# MM24I.net
KiCad netlist of a schematic drawn in EAGLE
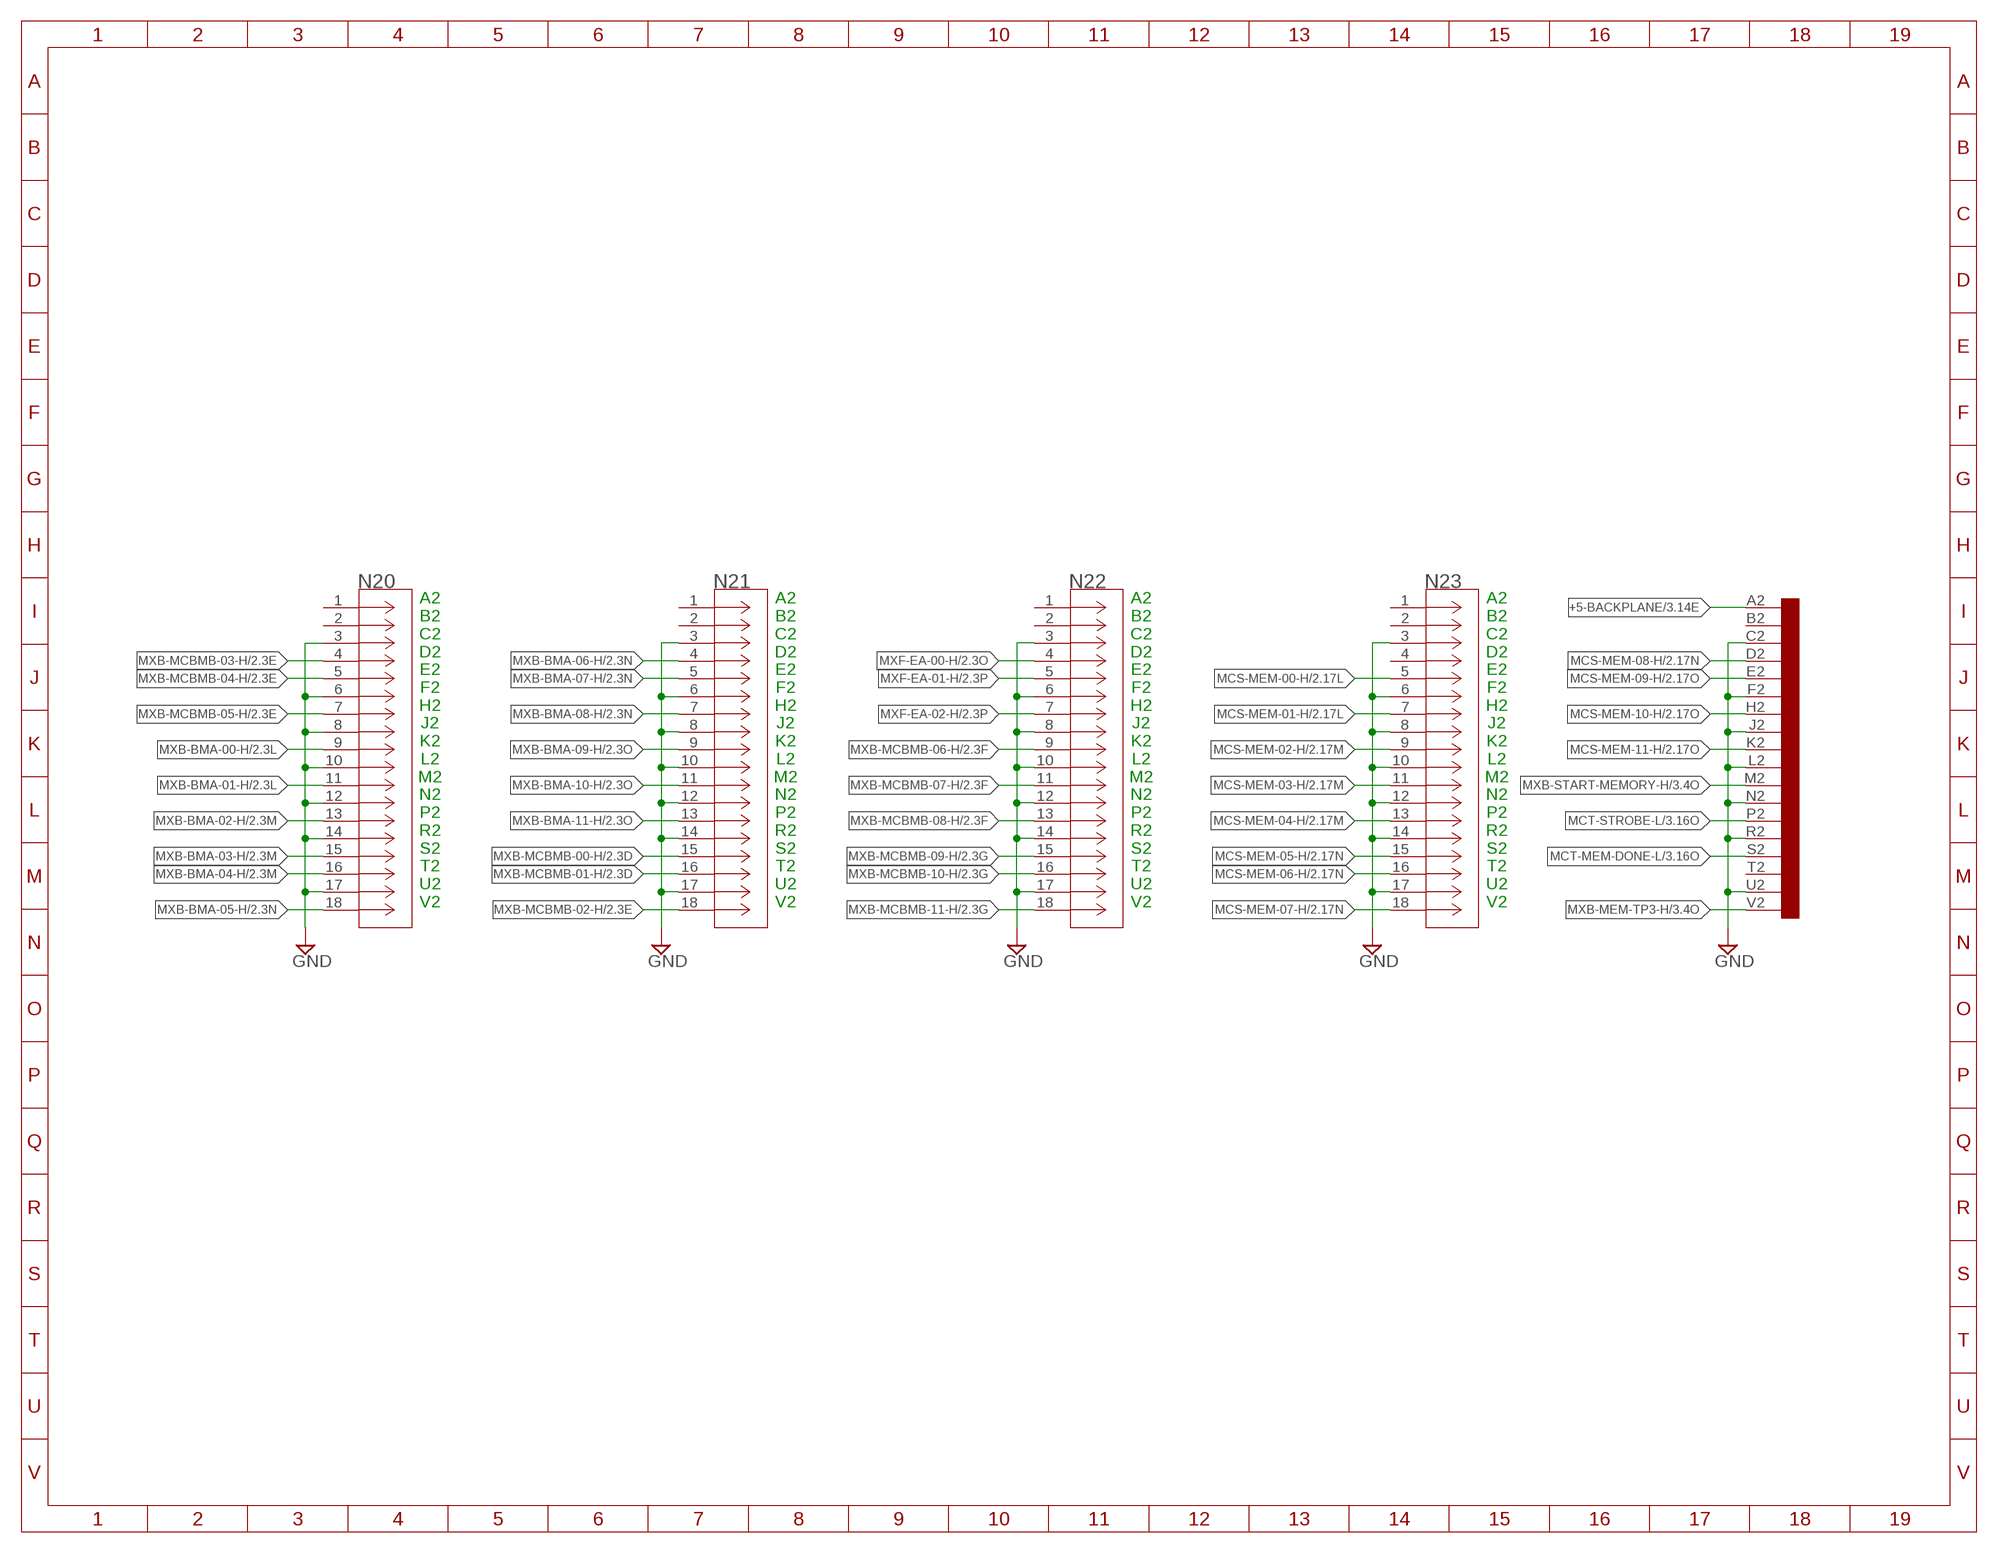
[diagram p0: schematic, sheet 1]
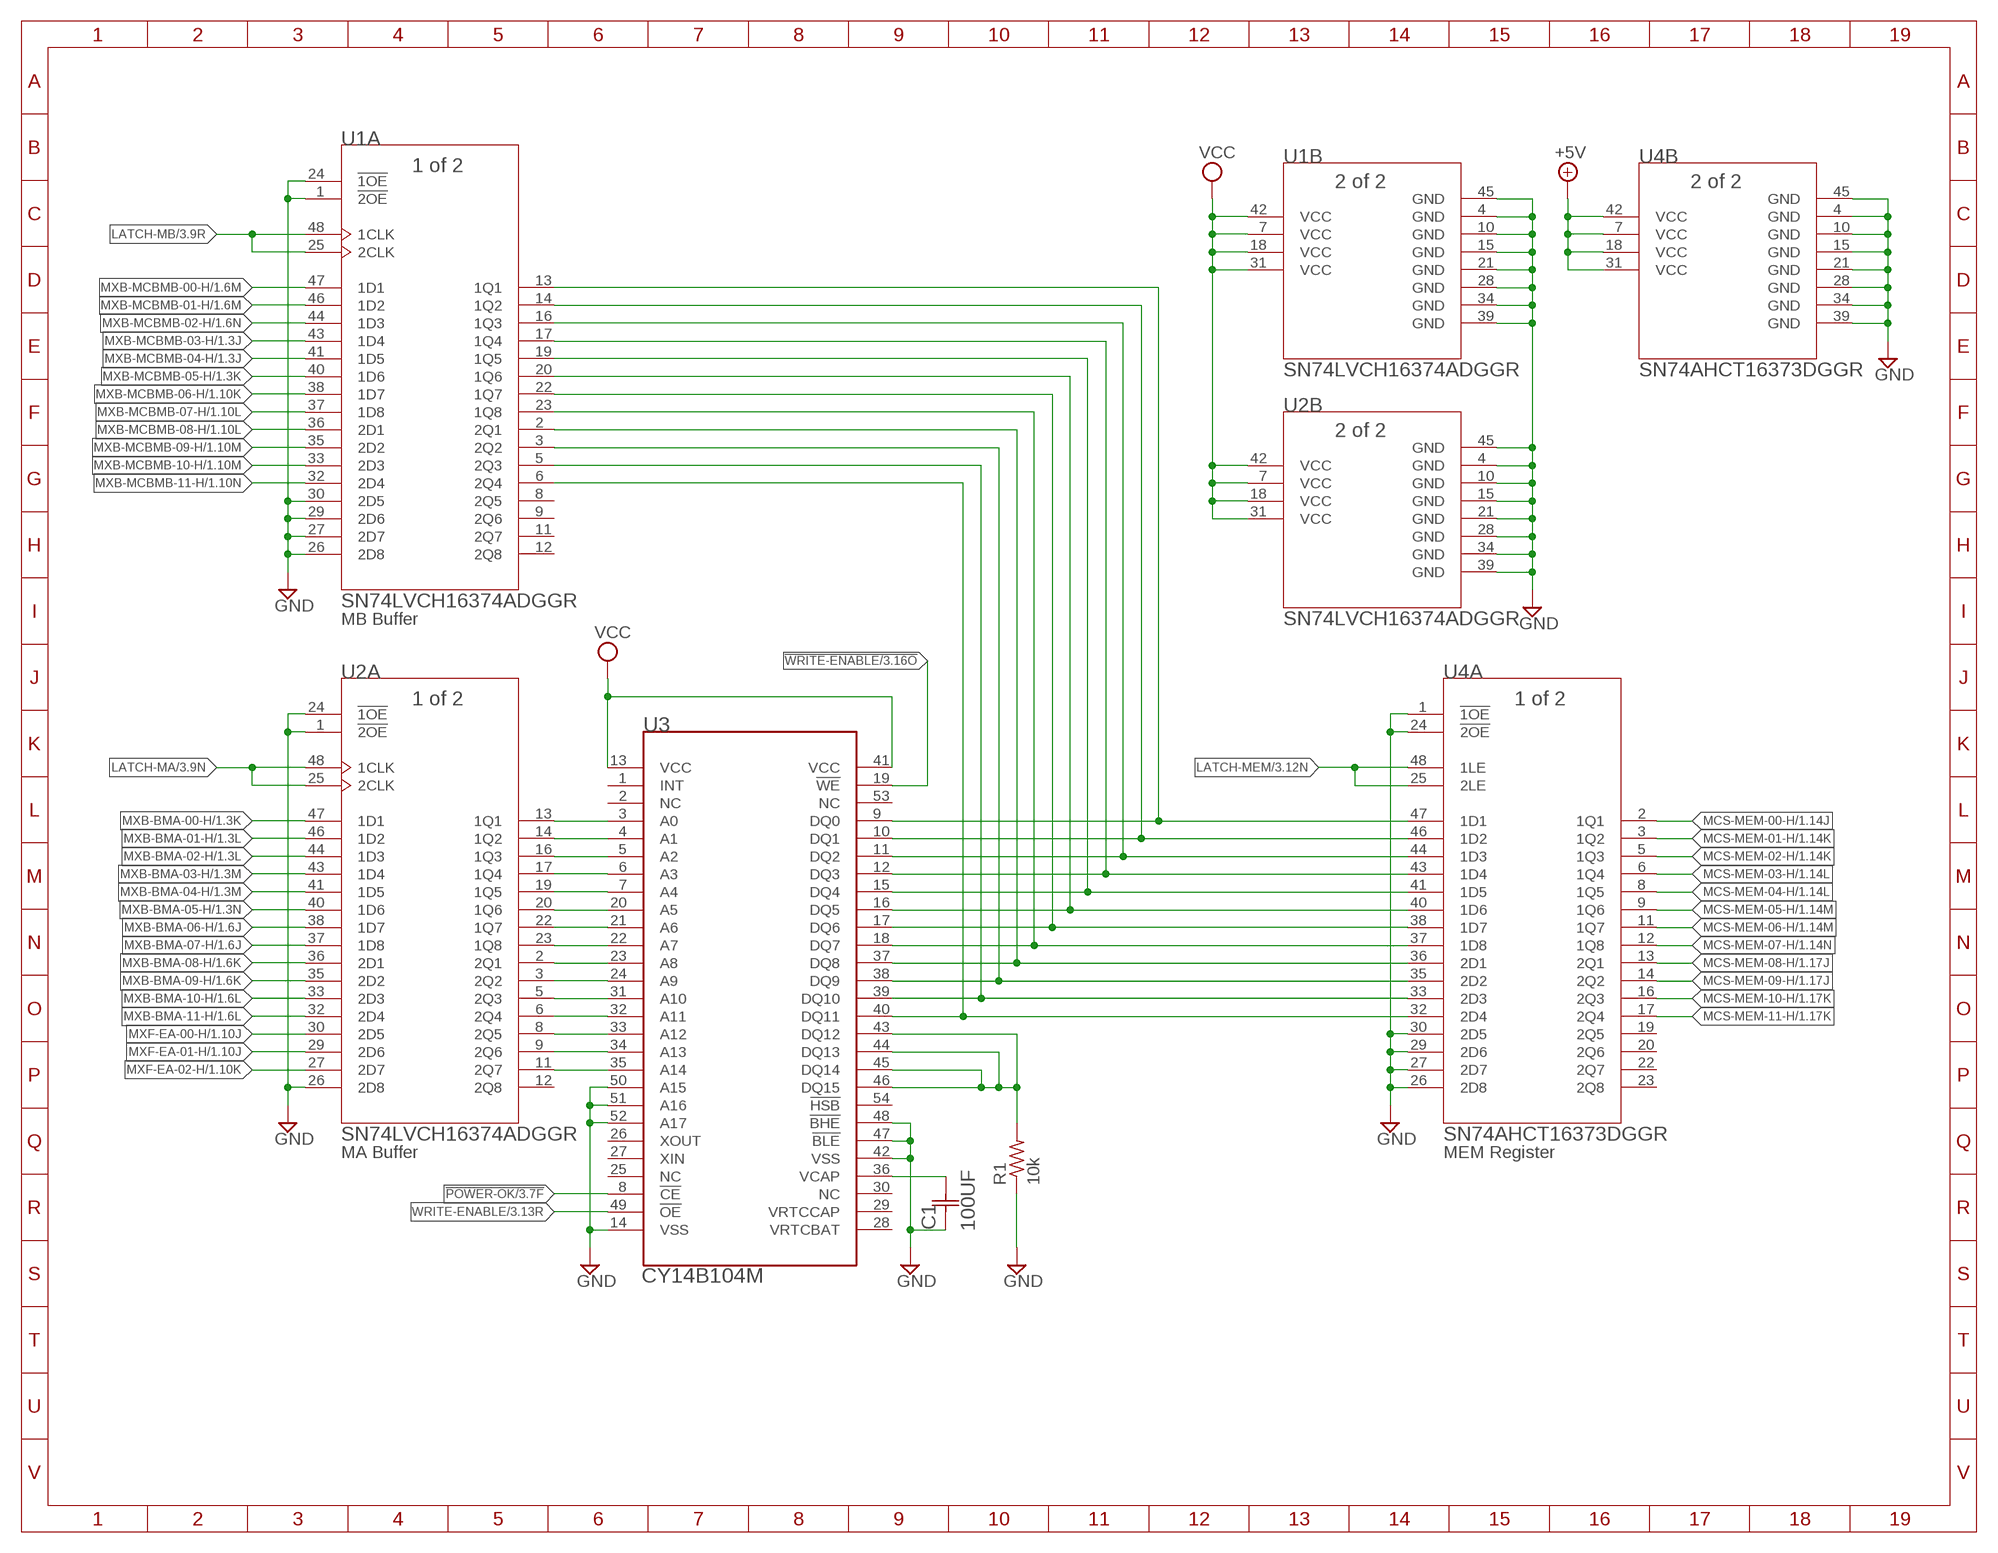
[diagram p1: schematic, sheet 2]
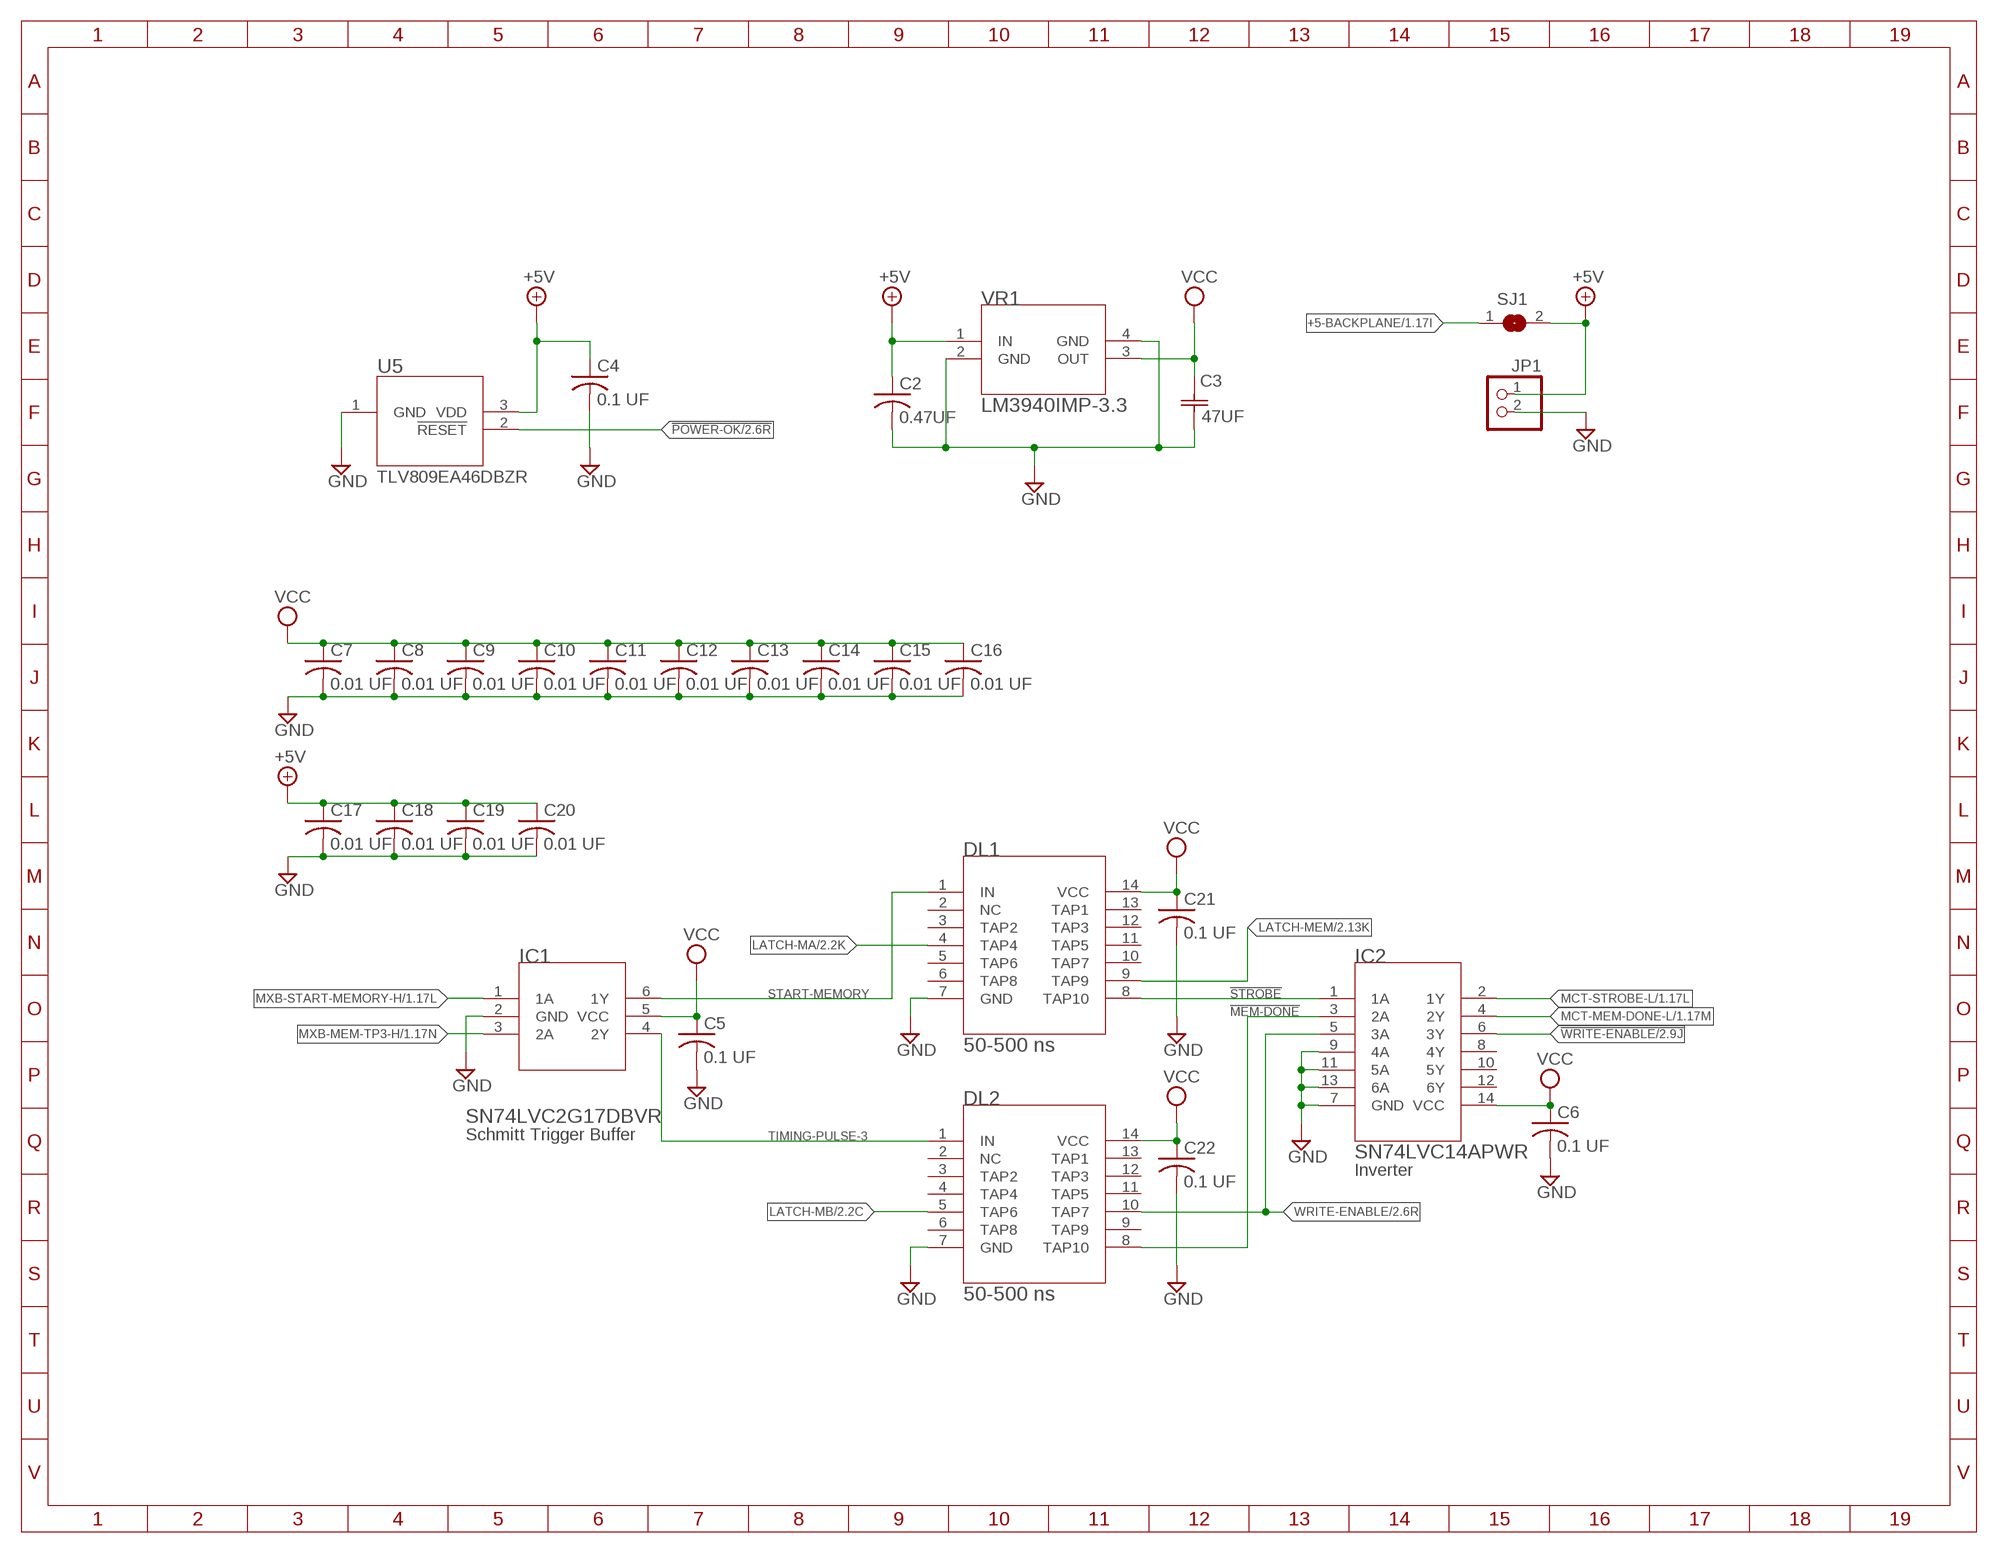
[diagram p2: schematic, sheet 3]

(export (version "E")
  (design (tool "Eeschema 10.0.6"))
  (components
    (comp (ref "C2")
      (value "0.47UF")
      (footprint "eagle-import:C0805")
      (libsource (lib "eagle-import") (part "C-USC0805"))
    )
    (comp (ref "C3")
      (value "47UF")
      (footprint "eagle-import:NOJC")
      (fields (field (name "MANUFACTURER_PART_NUMBER") "NOJC476M010RWJ"))
      (libsource (lib "eagle-import") (part "NOJC476M010RWJ"))
    )
    (comp (ref "C4")
      (value "0.1 UF")
      (footprint "eagle-import:C0402")
      (libsource (lib "eagle-import") (part "C-USC0402"))
    )
    (comp (ref "C5")
      (value "0.1 UF")
      (footprint "eagle-import:C0402")
      (libsource (lib "eagle-import") (part "C-USC0402"))
    )
    (comp (ref "C6")
      (value "0.1 UF")
      (footprint "eagle-import:C0402")
      (libsource (lib "eagle-import") (part "C-USC0402"))
    )
    (comp (ref "C7")
      (value "0.01 UF")
      (footprint "eagle-import:C0402")
      (libsource (lib "eagle-import") (part "C-USC0402"))
    )
    (comp (ref "C8")
      (value "0.01 UF")
      (footprint "eagle-import:C0402")
      (libsource (lib "eagle-import") (part "C-USC0402"))
    )
    (comp (ref "C9")
      (value "0.01 UF")
      (footprint "eagle-import:C0402")
      (libsource (lib "eagle-import") (part "C-USC0402"))
    )
    (comp (ref "C10")
      (value "0.01 UF")
      (footprint "eagle-import:C0402")
      (libsource (lib "eagle-import") (part "C-USC0402"))
    )
    (comp (ref "C11")
      (value "0.01 UF")
      (footprint "eagle-import:C0402")
      (libsource (lib "eagle-import") (part "C-USC0402"))
    )
    (comp (ref "C12")
      (value "0.01 UF")
      (footprint "eagle-import:C0402")
      (libsource (lib "eagle-import") (part "C-USC0402"))
    )
    (comp (ref "C13")
      (value "0.01 UF")
      (footprint "eagle-import:C0402")
      (libsource (lib "eagle-import") (part "C-USC0402"))
    )
    (comp (ref "C14")
      (value "0.01 UF")
      (footprint "eagle-import:C0402")
      (libsource (lib "eagle-import") (part "C-USC0402"))
    )
    (comp (ref "C15")
      (value "0.01 UF")
      (footprint "eagle-import:C0402")
      (libsource (lib "eagle-import") (part "C-USC0402"))
    )
    (comp (ref "C16")
      (value "0.01 UF")
      (footprint "eagle-import:C0402")
      (libsource (lib "eagle-import") (part "C-USC0402"))
    )
    (comp (ref "C17")
      (value "0.01 UF")
      (footprint "eagle-import:C0402")
      (libsource (lib "eagle-import") (part "C-USC0402"))
    )
    (comp (ref "C18")
      (value "0.01 UF")
      (footprint "eagle-import:C0402")
      (libsource (lib "eagle-import") (part "C-USC0402"))
    )
    (comp (ref "C19")
      (value "0.01 UF")
      (footprint "eagle-import:C0402")
      (libsource (lib "eagle-import") (part "C-USC0402"))
    )
    (comp (ref "C20")
      (value "0.01 UF")
      (footprint "eagle-import:C0402")
      (libsource (lib "eagle-import") (part "C-USC0402"))
    )
    (comp (ref "C21")
      (value "0.1 UF")
      (footprint "eagle-import:C0402")
      (libsource (lib "eagle-import") (part "C-USC0402"))
    )
    (comp (ref "C22")
      (value "0.1 UF")
      (footprint "eagle-import:C0402")
      (libsource (lib "eagle-import") (part "C-USC0402"))
    )
    (comp (ref "DL1")
      (value "50-500 ns")
      (footprint "eagle-import:21-0066J_14")
      (fields (field (name "MANUFACTURER_PART_NUMBER") "DS1110LE-100+"))
      (libsource (lib "eagle-import") (part "DS1110LE-500+"))
    )
    (comp (ref "DL2")
      (value "50-500 ns")
      (footprint "eagle-import:21-0066J_14")
      (fields (field (name "MANUFACTURER_PART_NUMBER") "DS1110LE-100+"))
      (libsource (lib "eagle-import") (part "DS1110LE-500+"))
    )
    (comp (ref "IC1")
      (value "SN74LVC2G17DBVR")
      (footprint "eagle-import:DBV6")
      (fields (field (name "MANUFACTURER") "Texas Instruments"))
      (libsource (lib "eagle-import") (part "SN74LVC2G17DBVR"))
    )
    (comp (ref "IC2")
      (value "SN74LVC14APWR")
      (footprint "eagle-import:PW14")
      (fields (field (name "MANUFACTURER") "Texas Instruments"))
      (libsource (lib "eagle-import") (part "SN74LVC14APWR"))
    )
    (comp (ref "JP1")
      (value "PINHD-1X2")
      (footprint "eagle-import:1X02")
      (libsource (lib "eagle-import") (part "PINHD-1X2"))
    )
    (comp (ref "SJ1") (value "SJ") (footprint "eagle-import:SJ") (libsource (lib "eagle-import") (part "SJ")))
    (comp (ref "U5")
      (value "TLV809EA46DBZR")
      (footprint "eagle-import:DBZ3")
      (fields (field (name "MANUFACTURER") "Texas Instruments"))
      (libsource (lib "eagle-import") (part "TLV809EA46DBZR"))
    )
    (comp (ref "VR1")
      (value "LM3940IMP-3.3")
      (footprint "eagle-import:MP04A")
      (fields (field (name "MANUFACTURER_PART_NUMBER") "LM3940IMP-3.3/NOPB"))
      (libsource (lib "eagle-import") (part "LM3940IMP-3.3"))
    )
    (comp (ref "N20")
      (value "FH12-18S-0.5SV(55)")
      (footprint "eagle-import:CON18_1X18_DUTB_HRS")
      (libsource (lib "eagle-import") (part "FH12-18S-0.5SV(55)"))
    )
    (comp (ref "N21")
      (value "FH12-18S-0.5SV(55)")
      (footprint "eagle-import:CON18_1X18_DUTB_HRS")
      (libsource (lib "eagle-import") (part "FH12-18S-0.5SV(55)"))
    )
    (comp (ref "N22")
      (value "FH12-18S-0.5SV(55)")
      (footprint "eagle-import:CON18_1X18_DUTB_HRS")
      (libsource (lib "eagle-import") (part "FH12-18S-0.5SV(55)"))
    )
    (comp (ref "N23")
      (value "FH12-18S-0.5SV(55)")
      (footprint "eagle-import:CON18_1X18_DUTB_HRS")
      (libsource (lib "eagle-import") (part "FH12-18S-0.5SV(55)"))
    )
    (comp (ref "U$1")
      (value "SINGLE")
      (footprint "eagle-import:EDGE-CON2")
      (libsource (lib "eagle-import") (part "SINGLE"))
    )
    (comp (ref "C1")
      (value "100UF")
      (footprint "eagle-import:CAPCP7343X430N")
      (fields (field (name "MPN") "NOJD107M010RWJ"))
      (libsource (lib "eagle-import") (part "NOJD107M010RWJ"))
    )
    (comp (ref "R1")
      (value "10k")
      (footprint "eagle-import:R0402")
      (libsource (lib "eagle-import") (part "R-US_R0402"))
    )
    (comp (ref "U1")
      (value "SN74LVCH16374ADGGR")
      (footprint "eagle-import:DGG48")
      (libsource (lib "eagle-import") (part "SN74LVCH16374ADGGR"))
    )
    (comp (ref "U2")
      (value "SN74LVCH16374ADGGR")
      (footprint "eagle-import:DGG48")
      (libsource (lib "eagle-import") (part "SN74LVCH16374ADGGR"))
    )
    (comp (ref "U3")
      (value "CY14B104M")
      (footprint "eagle-import:TSOPII-54")
      (libsource (lib "eagle-import") (part "CY14B104M"))
    )
    (comp (ref "U4")
      (value "SN74AHCT16373DGGR")
      (footprint "eagle-import:DGG48")
      (fields (field (name "MANUFACTURER") "Texas Instruments"))
      (libsource (lib "eagle-import") (part "SN74AHCT16373DGGR"))
    )
  )
  (nets
    (net (code "1") (name "+5-BACKPLANE") (class "Default")
      (node (ref "SJ1") (pin "1") (pinfunction "1_1") (pintype "passive"))
      (node (ref "U$1") (pin "A2") (pinfunction "1_A2") (pintype "bidirectional"))
    )
    (net (code "2") (name "+5V") (class "Default")
      (node (ref "C17") (pin "1") (pinfunction "1_1") (pintype "passive"))
      (node (ref "C18") (pin "1") (pinfunction "1_1") (pintype "passive"))
      (node (ref "C19") (pin "1") (pinfunction "1_1") (pintype "passive"))
      (node (ref "C2") (pin "1") (pinfunction "1_1") (pintype "passive"))
      (node (ref "C20") (pin "1") (pinfunction "1_1") (pintype "passive"))
      (node (ref "C4") (pin "1") (pinfunction "1_1") (pintype "passive"))
      (node (ref "JP1") (pin "1") (pinfunction "1_1") (pintype "passive"))
      (node (ref "SJ1") (pin "2") (pinfunction "2_2") (pintype "passive"))
      (node (ref "U4") (pin "18") (pinfunction "VCC_18") (pintype "power_in"))
      (node (ref "U4") (pin "31") (pinfunction "VCC_31") (pintype "power_in"))
      (node (ref "U4") (pin "42") (pinfunction "VCC_42") (pintype "power_in"))
      (node (ref "U4") (pin "7") (pinfunction "VCC_7") (pintype "power_in"))
      (node (ref "U5") (pin "3") (pinfunction "VDD_3") (pintype "power_in"))
      (node (ref "VR1") (pin "1") (pinfunction "IN_1") (pintype "input"))
    )
    (net (code "3") (name "GND") (class "Default")
      (node (ref "C1") (pin "2") (pinfunction "C2_2") (pintype "passive"))
      (node (ref "C10") (pin "2") (pinfunction "2_2") (pintype "passive"))
      (node (ref "C11") (pin "2") (pinfunction "2_2") (pintype "passive"))
      (node (ref "C12") (pin "2") (pinfunction "2_2") (pintype "passive"))
      (node (ref "C13") (pin "2") (pinfunction "2_2") (pintype "passive"))
      (node (ref "C14") (pin "2") (pinfunction "2_2") (pintype "passive"))
      (node (ref "C15") (pin "2") (pinfunction "2_2") (pintype "passive"))
      (node (ref "C16") (pin "2") (pinfunction "2_2") (pintype "passive"))
      (node (ref "C17") (pin "2") (pinfunction "2_2") (pintype "passive"))
      (node (ref "C18") (pin "2") (pinfunction "2_2") (pintype "passive"))
      (node (ref "C19") (pin "2") (pinfunction "2_2") (pintype "passive"))
      (node (ref "C2") (pin "2") (pinfunction "2_2") (pintype "passive"))
      (node (ref "C20") (pin "2") (pinfunction "2_2") (pintype "passive"))
      (node (ref "C21") (pin "2") (pinfunction "2_2") (pintype "passive"))
      (node (ref "C22") (pin "2") (pinfunction "2_2") (pintype "passive"))
      (node (ref "C3") (pin "2") (pinfunction "C2_2") (pintype "passive"))
      (node (ref "C4") (pin "2") (pinfunction "2_2") (pintype "passive"))
      (node (ref "C5") (pin "2") (pinfunction "2_2") (pintype "passive"))
      (node (ref "C6") (pin "2") (pinfunction "2_2") (pintype "passive"))
      (node (ref "C7") (pin "2") (pinfunction "2_2") (pintype "passive"))
      (node (ref "C8") (pin "2") (pinfunction "2_2") (pintype "passive"))
      (node (ref "C9") (pin "2") (pinfunction "2_2") (pintype "passive"))
      (node (ref "DL1") (pin "7") (pinfunction "GND_7") (pintype "power_in"))
      (node (ref "DL2") (pin "7") (pinfunction "GND_7") (pintype "power_in"))
      (node (ref "IC1") (pin "2") (pinfunction "GND_2") (pintype "power_in"))
      (node (ref "IC2") (pin "11") (pinfunction "5A_11") (pintype "input"))
      (node (ref "IC2") (pin "13") (pinfunction "6A_13") (pintype "input"))
      (node (ref "IC2") (pin "7") (pinfunction "GND_7") (pintype "power_in"))
      (node (ref "IC2") (pin "9") (pinfunction "4A_9") (pintype "input"))
      (node (ref "JP1") (pin "2") (pinfunction "2_2") (pintype "passive"))
      (node (ref "N20") (pin "10") (pinfunction "10_10") (pintype "passive"))
      (node (ref "N20") (pin "12") (pinfunction "12_12") (pintype "passive"))
      (node (ref "N20") (pin "14") (pinfunction "14_14") (pintype "passive"))
      (node (ref "N20") (pin "17") (pinfunction "17_17") (pintype "passive"))
      (node (ref "N20") (pin "3") (pinfunction "3_3") (pintype "passive"))
      (node (ref "N20") (pin "6") (pinfunction "6_6") (pintype "passive"))
      (node (ref "N20") (pin "8") (pinfunction "8_8") (pintype "passive"))
      (node (ref "N21") (pin "10") (pinfunction "10_10") (pintype "passive"))
      (node (ref "N21") (pin "12") (pinfunction "12_12") (pintype "passive"))
      (node (ref "N21") (pin "14") (pinfunction "14_14") (pintype "passive"))
      (node (ref "N21") (pin "17") (pinfunction "17_17") (pintype "passive"))
      (node (ref "N21") (pin "3") (pinfunction "3_3") (pintype "passive"))
      (node (ref "N21") (pin "6") (pinfunction "6_6") (pintype "passive"))
      (node (ref "N21") (pin "8") (pinfunction "8_8") (pintype "passive"))
      (node (ref "N22") (pin "10") (pinfunction "10_10") (pintype "passive"))
      (node (ref "N22") (pin "12") (pinfunction "12_12") (pintype "passive"))
      (node (ref "N22") (pin "14") (pinfunction "14_14") (pintype "passive"))
      (node (ref "N22") (pin "17") (pinfunction "17_17") (pintype "passive"))
      (node (ref "N22") (pin "3") (pinfunction "3_3") (pintype "passive"))
      (node (ref "N22") (pin "6") (pinfunction "6_6") (pintype "passive"))
      (node (ref "N22") (pin "8") (pinfunction "8_8") (pintype "passive"))
      (node (ref "N23") (pin "10") (pinfunction "10_10") (pintype "passive"))
      (node (ref "N23") (pin "12") (pinfunction "12_12") (pintype "passive"))
      (node (ref "N23") (pin "14") (pinfunction "14_14") (pintype "passive"))
      (node (ref "N23") (pin "17") (pinfunction "17_17") (pintype "passive"))
      (node (ref "N23") (pin "3") (pinfunction "3_3") (pintype "passive"))
      (node (ref "N23") (pin "6") (pinfunction "6_6") (pintype "passive"))
      (node (ref "N23") (pin "8") (pinfunction "8_8") (pintype "passive"))
      (node (ref "R1") (pin "1") (pinfunction "1_1") (pintype "passive"))
      (node (ref "U$1") (pin "C2") (pinfunction "1_C2") (pintype "bidirectional"))
      (node (ref "U$1") (pin "F2") (pinfunction "1_F2") (pintype "bidirectional"))
      (node (ref "U$1") (pin "J2") (pinfunction "1_J2") (pintype "bidirectional"))
      (node (ref "U$1") (pin "L2") (pinfunction "1_L2") (pintype "bidirectional"))
      (node (ref "U$1") (pin "N2") (pinfunction "1_N2") (pintype "bidirectional"))
      (node (ref "U$1") (pin "R2") (pinfunction "1_R2") (pintype "bidirectional"))
      (node (ref "U$1") (pin "U2") (pinfunction "1_U2") (pintype "bidirectional"))
      (node (ref "U1") (pin "1") (pinfunction "~{2OE}_1") (pintype "input"))
      (node (ref "U1") (pin "10") (pinfunction "GND_10") (pintype "power_in"))
      (node (ref "U1") (pin "15") (pinfunction "GND_15") (pintype "power_in"))
      (node (ref "U1") (pin "21") (pinfunction "GND_21") (pintype "power_in"))
      (node (ref "U1") (pin "24") (pinfunction "~{1OE}_24") (pintype "input"))
      (node (ref "U1") (pin "26") (pinfunction "2D8_26") (pintype "input"))
      (node (ref "U1") (pin "27") (pinfunction "2D7_27") (pintype "input"))
      (node (ref "U1") (pin "28") (pinfunction "GND_28") (pintype "power_in"))
      (node (ref "U1") (pin "29") (pinfunction "2D6_29") (pintype "input"))
      (node (ref "U1") (pin "30") (pinfunction "2D5_30") (pintype "input"))
      (node (ref "U1") (pin "34") (pinfunction "GND_34") (pintype "power_in"))
      (node (ref "U1") (pin "39") (pinfunction "GND_39") (pintype "power_in"))
      (node (ref "U1") (pin "4") (pinfunction "GND_4") (pintype "power_in"))
      (node (ref "U1") (pin "45") (pinfunction "GND_45") (pintype "power_in"))
      (node (ref "U2") (pin "1") (pinfunction "~{2OE}_1") (pintype "input"))
      (node (ref "U2") (pin "10") (pinfunction "GND_10") (pintype "power_in"))
      (node (ref "U2") (pin "15") (pinfunction "GND_15") (pintype "power_in"))
      (node (ref "U2") (pin "21") (pinfunction "GND_21") (pintype "power_in"))
      (node (ref "U2") (pin "24") (pinfunction "~{1OE}_24") (pintype "input"))
      (node (ref "U2") (pin "26") (pinfunction "2D8_26") (pintype "input"))
      (node (ref "U2") (pin "28") (pinfunction "GND_28") (pintype "power_in"))
      (node (ref "U2") (pin "34") (pinfunction "GND_34") (pintype "power_in"))
      (node (ref "U2") (pin "39") (pinfunction "GND_39") (pintype "power_in"))
      (node (ref "U2") (pin "4") (pinfunction "GND_4") (pintype "power_in"))
      (node (ref "U2") (pin "45") (pinfunction "GND_45") (pintype "power_in"))
      (node (ref "U3") (pin "14") (pinfunction "VSS_14") (pintype "power_in"))
      (node (ref "U3") (pin "42") (pinfunction "VSS_42") (pintype "power_in"))
      (node (ref "U3") (pin "47") (pinfunction "~{BLE}_47") (pintype "input"))
      (node (ref "U3") (pin "48") (pinfunction "~{BHE}_48") (pintype "input"))
      (node (ref "U3") (pin "50") (pinfunction "A15_50") (pintype "input"))
      (node (ref "U3") (pin "51") (pinfunction "A16_51") (pintype "input"))
      (node (ref "U3") (pin "52") (pinfunction "A17_52") (pintype "input"))
      (node (ref "U4") (pin "1") (pinfunction "~{1OE}_1") (pintype "input"))
      (node (ref "U4") (pin "10") (pinfunction "GND_10") (pintype "power_in"))
      (node (ref "U4") (pin "15") (pinfunction "GND_15") (pintype "power_in"))
      (node (ref "U4") (pin "21") (pinfunction "GND_21") (pintype "power_in"))
      (node (ref "U4") (pin "24") (pinfunction "~{2OE}_24") (pintype "input"))
      (node (ref "U4") (pin "26") (pinfunction "2D8_26") (pintype "input"))
      (node (ref "U4") (pin "27") (pinfunction "2D7_27") (pintype "input"))
      (node (ref "U4") (pin "28") (pinfunction "GND_28") (pintype "power_in"))
      (node (ref "U4") (pin "29") (pinfunction "2D6_29") (pintype "input"))
      (node (ref "U4") (pin "30") (pinfunction "2D5_30") (pintype "input"))
      (node (ref "U4") (pin "34") (pinfunction "GND_34") (pintype "power_in"))
      (node (ref "U4") (pin "39") (pinfunction "GND_39") (pintype "power_in"))
      (node (ref "U4") (pin "4") (pinfunction "GND_4") (pintype "power_in"))
      (node (ref "U4") (pin "45") (pinfunction "GND_45") (pintype "power_in"))
      (node (ref "U5") (pin "1") (pinfunction "GND_1") (pintype "power_in"))
      (node (ref "VR1") (pin "2") (pinfunction "GND_2") (pintype "passive"))
      (node (ref "VR1") (pin "4") (pinfunction "GND_4") (pintype "passive"))
    )
    (net (code "4") (name "LATCH-MA") (class "Default")
      (node (ref "DL1") (pin "4") (pinfunction "TAP4_4") (pintype "output"))
      (node (ref "U2") (pin "25") (pinfunction "2CLK_25") (pintype "input"))
      (node (ref "U2") (pin "48") (pinfunction "1CLK_48") (pintype "input"))
    )
    (net (code "5") (name "LATCH-MB") (class "Default")
      (node (ref "DL2") (pin "5") (pinfunction "TAP6_5") (pintype "output"))
      (node (ref "U1") (pin "25") (pinfunction "2CLK_25") (pintype "input"))
      (node (ref "U1") (pin "48") (pinfunction "1CLK_48") (pintype "input"))
    )
    (net (code "6") (name "LATCH-MEM") (class "Default")
      (node (ref "DL1") (pin "9") (pinfunction "TAP9_9") (pintype "output"))
      (node (ref "U4") (pin "25") (pinfunction "2LE_25") (pintype "input"))
      (node (ref "U4") (pin "48") (pinfunction "1LE_48") (pintype "input"))
    )
    (net (code "7") (name "MCS-MEM-00-H") (class "Default")
      (node (ref "N23") (pin "5") (pinfunction "5_5") (pintype "passive"))
      (node (ref "U4") (pin "2") (pinfunction "1Q1_2") (pintype "output"))
    )
    (net (code "8") (name "MCS-MEM-01-H") (class "Default")
      (node (ref "N23") (pin "7") (pinfunction "7_7") (pintype "passive"))
      (node (ref "U4") (pin "3") (pinfunction "1Q2_3") (pintype "output"))
    )
    (net (code "9") (name "MCS-MEM-02-H") (class "Default")
      (node (ref "N23") (pin "9") (pinfunction "9_9") (pintype "passive"))
      (node (ref "U4") (pin "5") (pinfunction "1Q3_5") (pintype "output"))
    )
    (net (code "10") (name "MCS-MEM-03-H") (class "Default")
      (node (ref "N23") (pin "11") (pinfunction "11_11") (pintype "passive"))
      (node (ref "U4") (pin "6") (pinfunction "1Q4_6") (pintype "output"))
    )
    (net (code "11") (name "MCS-MEM-04-H") (class "Default")
      (node (ref "N23") (pin "13") (pinfunction "13_13") (pintype "passive"))
      (node (ref "U4") (pin "8") (pinfunction "1Q5_8") (pintype "output"))
    )
    (net (code "12") (name "MCS-MEM-05-H") (class "Default")
      (node (ref "N23") (pin "15") (pinfunction "15_15") (pintype "passive"))
      (node (ref "U4") (pin "9") (pinfunction "1Q6_9") (pintype "output"))
    )
    (net (code "13") (name "MCS-MEM-06-H") (class "Default")
      (node (ref "N23") (pin "16") (pinfunction "16_16") (pintype "passive"))
      (node (ref "U4") (pin "11") (pinfunction "1Q7_11") (pintype "output"))
    )
    (net (code "14") (name "MCS-MEM-07-H") (class "Default")
      (node (ref "N23") (pin "18") (pinfunction "18_18") (pintype "passive"))
      (node (ref "U4") (pin "12") (pinfunction "1Q8_12") (pintype "output"))
    )
    (net (code "15") (name "MCS-MEM-08-H") (class "Default")
      (node (ref "U$1") (pin "D2") (pinfunction "1_D2") (pintype "bidirectional"))
      (node (ref "U4") (pin "13") (pinfunction "2Q1_13") (pintype "output"))
    )
    (net (code "16") (name "MCS-MEM-09-H") (class "Default")
      (node (ref "U$1") (pin "E2") (pinfunction "1_E2") (pintype "bidirectional"))
      (node (ref "U4") (pin "14") (pinfunction "2Q2_14") (pintype "output"))
    )
    (net (code "17") (name "MCS-MEM-10-H") (class "Default")
      (node (ref "U$1") (pin "H2") (pinfunction "1_H2") (pintype "bidirectional"))
      (node (ref "U4") (pin "16") (pinfunction "2Q3_16") (pintype "output"))
    )
    (net (code "18") (name "MCS-MEM-11-H") (class "Default")
      (node (ref "U$1") (pin "K2") (pinfunction "1_K2") (pintype "bidirectional"))
      (node (ref "U4") (pin "17") (pinfunction "2Q4_17") (pintype "output"))
    )
    (net (code "19") (name "MCT-MEM-DONE-L") (class "Default")
      (node (ref "IC2") (pin "4") (pinfunction "2Y_4") (pintype "output"))
      (node (ref "U$1") (pin "S2") (pinfunction "1_S2") (pintype "bidirectional"))
    )
    (net (code "20") (name "MCT-STROBE-L") (class "Default")
      (node (ref "IC2") (pin "2") (pinfunction "1Y_2") (pintype "output"))
      (node (ref "U$1") (pin "P2") (pinfunction "1_P2") (pintype "bidirectional"))
    )
    (net (code "21") (name "MXB-BMA-00-H") (class "Default")
      (node (ref "N20") (pin "9") (pinfunction "9_9") (pintype "passive"))
      (node (ref "U2") (pin "47") (pinfunction "1D1_47") (pintype "input"))
    )
    (net (code "22") (name "MXB-BMA-01-H") (class "Default")
      (node (ref "N20") (pin "11") (pinfunction "11_11") (pintype "passive"))
      (node (ref "U2") (pin "46") (pinfunction "1D2_46") (pintype "input"))
    )
    (net (code "23") (name "MXB-BMA-02-H") (class "Default")
      (node (ref "N20") (pin "13") (pinfunction "13_13") (pintype "passive"))
      (node (ref "U2") (pin "44") (pinfunction "1D3_44") (pintype "input"))
    )
    (net (code "24") (name "MXB-BMA-03-H") (class "Default")
      (node (ref "N20") (pin "15") (pinfunction "15_15") (pintype "passive"))
      (node (ref "U2") (pin "43") (pinfunction "1D4_43") (pintype "input"))
    )
    (net (code "25") (name "MXB-BMA-04-H") (class "Default")
      (node (ref "N20") (pin "16") (pinfunction "16_16") (pintype "passive"))
      (node (ref "U2") (pin "41") (pinfunction "1D5_41") (pintype "input"))
    )
    (net (code "26") (name "MXB-BMA-05-H") (class "Default")
      (node (ref "N20") (pin "18") (pinfunction "18_18") (pintype "passive"))
      (node (ref "U2") (pin "40") (pinfunction "1D6_40") (pintype "input"))
    )
    (net (code "27") (name "MXB-BMA-06-H") (class "Default")
      (node (ref "N21") (pin "4") (pinfunction "4_4") (pintype "passive"))
      (node (ref "U2") (pin "38") (pinfunction "1D7_38") (pintype "input"))
    )
    (net (code "28") (name "MXB-BMA-07-H") (class "Default")
      (node (ref "N21") (pin "5") (pinfunction "5_5") (pintype "passive"))
      (node (ref "U2") (pin "37") (pinfunction "1D8_37") (pintype "input"))
    )
    (net (code "29") (name "MXB-BMA-08-H") (class "Default")
      (node (ref "N21") (pin "7") (pinfunction "7_7") (pintype "passive"))
      (node (ref "U2") (pin "36") (pinfunction "2D1_36") (pintype "input"))
    )
    (net (code "30") (name "MXB-BMA-09-H") (class "Default")
      (node (ref "N21") (pin "9") (pinfunction "9_9") (pintype "passive"))
      (node (ref "U2") (pin "35") (pinfunction "2D2_35") (pintype "input"))
    )
    (net (code "31") (name "MXB-BMA-10-H") (class "Default")
      (node (ref "N21") (pin "11") (pinfunction "11_11") (pintype "passive"))
      (node (ref "U2") (pin "33") (pinfunction "2D3_33") (pintype "input"))
    )
    (net (code "32") (name "MXB-BMA-11-H") (class "Default")
      (node (ref "N21") (pin "13") (pinfunction "13_13") (pintype "passive"))
      (node (ref "U2") (pin "32") (pinfunction "2D4_32") (pintype "input"))
    )
    (net (code "33") (name "MXB-MCBMB-00-H") (class "Default")
      (node (ref "N21") (pin "15") (pinfunction "15_15") (pintype "passive"))
      (node (ref "U1") (pin "47") (pinfunction "1D1_47") (pintype "input"))
    )
    (net (code "34") (name "MXB-MCBMB-01-H") (class "Default")
      (node (ref "N21") (pin "16") (pinfunction "16_16") (pintype "passive"))
      (node (ref "U1") (pin "46") (pinfunction "1D2_46") (pintype "input"))
    )
    (net (code "35") (name "MXB-MCBMB-02-H") (class "Default")
      (node (ref "N21") (pin "18") (pinfunction "18_18") (pintype "passive"))
      (node (ref "U1") (pin "44") (pinfunction "1D3_44") (pintype "input"))
    )
    (net (code "36") (name "MXB-MCBMB-03-H") (class "Default")
      (node (ref "N20") (pin "4") (pinfunction "4_4") (pintype "passive"))
      (node (ref "U1") (pin "43") (pinfunction "1D4_43") (pintype "input"))
    )
    (net (code "37") (name "MXB-MCBMB-04-H") (class "Default")
      (node (ref "N20") (pin "5") (pinfunction "5_5") (pintype "passive"))
      (node (ref "U1") (pin "41") (pinfunction "1D5_41") (pintype "input"))
    )
    (net (code "38") (name "MXB-MCBMB-05-H") (class "Default")
      (node (ref "N20") (pin "7") (pinfunction "7_7") (pintype "passive"))
      (node (ref "U1") (pin "40") (pinfunction "1D6_40") (pintype "input"))
    )
    (net (code "39") (name "MXB-MCBMB-06-H") (class "Default")
      (node (ref "N22") (pin "9") (pinfunction "9_9") (pintype "passive"))
      (node (ref "U1") (pin "38") (pinfunction "1D7_38") (pintype "input"))
    )
    (net (code "40") (name "MXB-MCBMB-07-H") (class "Default")
      (node (ref "N22") (pin "11") (pinfunction "11_11") (pintype "passive"))
      (node (ref "U1") (pin "37") (pinfunction "1D8_37") (pintype "input"))
    )
    (net (code "41") (name "MXB-MCBMB-08-H") (class "Default")
      (node (ref "N22") (pin "13") (pinfunction "13_13") (pintype "passive"))
      (node (ref "U1") (pin "36") (pinfunction "2D1_36") (pintype "input"))
    )
    (net (code "42") (name "MXB-MCBMB-09-H") (class "Default")
      (node (ref "N22") (pin "15") (pinfunction "15_15") (pintype "passive"))
      (node (ref "U1") (pin "35") (pinfunction "2D2_35") (pintype "input"))
    )
    (net (code "43") (name "MXB-MCBMB-10-H") (class "Default")
      (node (ref "N22") (pin "16") (pinfunction "16_16") (pintype "passive"))
      (node (ref "U1") (pin "33") (pinfunction "2D3_33") (pintype "input"))
    )
    (net (code "44") (name "MXB-MCBMB-11-H") (class "Default")
      (node (ref "N22") (pin "18") (pinfunction "18_18") (pintype "passive"))
      (node (ref "U1") (pin "32") (pinfunction "2D4_32") (pintype "input"))
    )
    (net (code "45") (name "MXB-MEM-TP3-H") (class "Default")
      (node (ref "IC1") (pin "3") (pinfunction "2A_3") (pintype "input"))
      (node (ref "U$1") (pin "V2") (pinfunction "1_V2") (pintype "bidirectional"))
    )
    (net (code "46") (name "MXB-START-MEMORY-H") (class "Default")
      (node (ref "IC1") (pin "1") (pinfunction "1A_1") (pintype "input"))
      (node (ref "U$1") (pin "M2") (pinfunction "1_M2") (pintype "bidirectional"))
    )
    (net (code "47") (name "MXF-EA-00-H") (class "Default")
      (node (ref "N22") (pin "4") (pinfunction "4_4") (pintype "passive"))
      (node (ref "U2") (pin "30") (pinfunction "2D5_30") (pintype "input"))
    )
    (net (code "48") (name "MXF-EA-01-H") (class "Default")
      (node (ref "N22") (pin "5") (pinfunction "5_5") (pintype "passive"))
      (node (ref "U2") (pin "29") (pinfunction "2D6_29") (pintype "input"))
    )
    (net (code "49") (name "MXF-EA-02-H") (class "Default")
      (node (ref "N22") (pin "7") (pinfunction "7_7") (pintype "passive"))
      (node (ref "U2") (pin "27") (pinfunction "2D7_27") (pintype "input"))
    )
    (net (code "50") (name "Net-(C1-C1)") (class "Default")
      (node (ref "C1") (pin "1") (pinfunction "C1_1") (pintype "passive"))
      (node (ref "U3") (pin "36") (pinfunction "VCAP_36") (pintype "output"))
    )
    (net (code "51") (name "Net-(U1A-1Q1)") (class "Default")
      (node (ref "U1") (pin "13") (pinfunction "1Q1_13") (pintype "output"))
      (node (ref "U3") (pin "9") (pinfunction "DQ0_9") (pintype "bidirectional"))
      (node (ref "U4") (pin "47") (pinfunction "1D1_47") (pintype "input"))
    )
    (net (code "52") (name "Net-(U1A-1Q2)") (class "Default")
      (node (ref "U1") (pin "14") (pinfunction "1Q2_14") (pintype "output"))
      (node (ref "U3") (pin "10") (pinfunction "DQ1_10") (pintype "bidirectional"))
      (node (ref "U4") (pin "46") (pinfunction "1D2_46") (pintype "input"))
    )
    (net (code "53") (name "Net-(U1A-1Q3)") (class "Default")
      (node (ref "U1") (pin "16") (pinfunction "1Q3_16") (pintype "output"))
      (node (ref "U3") (pin "11") (pinfunction "DQ2_11") (pintype "bidirectional"))
      (node (ref "U4") (pin "44") (pinfunction "1D3_44") (pintype "input"))
    )
    (net (code "54") (name "Net-(U1A-1Q4)") (class "Default")
      (node (ref "U1") (pin "17") (pinfunction "1Q4_17") (pintype "output"))
      (node (ref "U3") (pin "12") (pinfunction "DQ3_12") (pintype "bidirectional"))
      (node (ref "U4") (pin "43") (pinfunction "1D4_43") (pintype "input"))
    )
    (net (code "55") (name "Net-(U1A-1Q5)") (class "Default")
      (node (ref "U1") (pin "19") (pinfunction "1Q5_19") (pintype "output"))
      (node (ref "U3") (pin "15") (pinfunction "DQ4_15") (pintype "bidirectional"))
      (node (ref "U4") (pin "41") (pinfunction "1D5_41") (pintype "input"))
    )
    (net (code "56") (name "Net-(U1A-1Q6)") (class "Default")
      (node (ref "U1") (pin "20") (pinfunction "1Q6_20") (pintype "output"))
      (node (ref "U3") (pin "16") (pinfunction "DQ5_16") (pintype "bidirectional"))
      (node (ref "U4") (pin "40") (pinfunction "1D6_40") (pintype "input"))
    )
    (net (code "57") (name "Net-(U1A-1Q7)") (class "Default")
      (node (ref "U1") (pin "22") (pinfunction "1Q7_22") (pintype "output"))
      (node (ref "U3") (pin "17") (pinfunction "DQ6_17") (pintype "bidirectional"))
      (node (ref "U4") (pin "38") (pinfunction "1D7_38") (pintype "input"))
    )
    (net (code "58") (name "Net-(U1A-1Q8)") (class "Default")
      (node (ref "U1") (pin "23") (pinfunction "1Q8_23") (pintype "output"))
      (node (ref "U3") (pin "18") (pinfunction "DQ7_18") (pintype "bidirectional"))
      (node (ref "U4") (pin "37") (pinfunction "1D8_37") (pintype "input"))
    )
    (net (code "59") (name "Net-(U1A-2Q1)") (class "Default")
      (node (ref "U1") (pin "2") (pinfunction "2Q1_2") (pintype "output"))
      (node (ref "U3") (pin "37") (pinfunction "DQ8_37") (pintype "bidirectional"))
      (node (ref "U4") (pin "36") (pinfunction "2D1_36") (pintype "input"))
    )
    (net (code "60") (name "Net-(U1A-2Q2)") (class "Default")
      (node (ref "U1") (pin "3") (pinfunction "2Q2_3") (pintype "output"))
      (node (ref "U3") (pin "38") (pinfunction "DQ9_38") (pintype "bidirectional"))
      (node (ref "U4") (pin "35") (pinfunction "2D2_35") (pintype "input"))
    )
    (net (code "61") (name "Net-(U1A-2Q3)") (class "Default")
      (node (ref "U1") (pin "5") (pinfunction "2Q3_5") (pintype "output"))
      (node (ref "U3") (pin "39") (pinfunction "DQ10_39") (pintype "bidirectional"))
      (node (ref "U4") (pin "33") (pinfunction "2D3_33") (pintype "input"))
    )
    (net (code "62") (name "Net-(U1A-2Q4)") (class "Default")
      (node (ref "U1") (pin "6") (pinfunction "2Q4_6") (pintype "output"))
      (node (ref "U3") (pin "40") (pinfunction "DQ11_40") (pintype "bidirectional"))
      (node (ref "U4") (pin "32") (pinfunction "2D4_32") (pintype "input"))
    )
    (net (code "63") (name "Net-(U2A-1Q1)") (class "Default")
      (node (ref "U2") (pin "13") (pinfunction "1Q1_13") (pintype "output"))
      (node (ref "U3") (pin "3") (pinfunction "A0_3") (pintype "input"))
    )
    (net (code "64") (name "Net-(U2A-1Q2)") (class "Default")
      (node (ref "U2") (pin "14") (pinfunction "1Q2_14") (pintype "output"))
      (node (ref "U3") (pin "4") (pinfunction "A1_4") (pintype "input"))
    )
    (net (code "65") (name "Net-(U2A-1Q3)") (class "Default")
      (node (ref "U2") (pin "16") (pinfunction "1Q3_16") (pintype "output"))
      (node (ref "U3") (pin "5") (pinfunction "A2_5") (pintype "input"))
    )
    (net (code "66") (name "Net-(U2A-1Q4)") (class "Default")
      (node (ref "U2") (pin "17") (pinfunction "1Q4_17") (pintype "output"))
      (node (ref "U3") (pin "6") (pinfunction "A3_6") (pintype "input"))
    )
    (net (code "67") (name "Net-(U2A-1Q5)") (class "Default")
      (node (ref "U2") (pin "19") (pinfunction "1Q5_19") (pintype "output"))
      (node (ref "U3") (pin "7") (pinfunction "A4_7") (pintype "input"))
    )
    (net (code "68") (name "Net-(U2A-1Q6)") (class "Default")
      (node (ref "U2") (pin "20") (pinfunction "1Q6_20") (pintype "output"))
      (node (ref "U3") (pin "20") (pinfunction "A5_20") (pintype "input"))
    )
    (net (code "69") (name "Net-(U2A-1Q7)") (class "Default")
      (node (ref "U2") (pin "22") (pinfunction "1Q7_22") (pintype "output"))
      (node (ref "U3") (pin "21") (pinfunction "A6_21") (pintype "input"))
    )
    (net (code "70") (name "Net-(U2A-1Q8)") (class "Default")
      (node (ref "U2") (pin "23") (pinfunction "1Q8_23") (pintype "output"))
      (node (ref "U3") (pin "22") (pinfunction "A7_22") (pintype "input"))
    )
    (net (code "71") (name "Net-(U2A-2Q1)") (class "Default")
      (node (ref "U2") (pin "2") (pinfunction "2Q1_2") (pintype "output"))
      (node (ref "U3") (pin "23") (pinfunction "A8_23") (pintype "input"))
    )
    (net (code "72") (name "Net-(U2A-2Q2)") (class "Default")
      (node (ref "U2") (pin "3") (pinfunction "2Q2_3") (pintype "output"))
      (node (ref "U3") (pin "24") (pinfunction "A9_24") (pintype "input"))
    )
    (net (code "73") (name "Net-(U2A-2Q3)") (class "Default")
      (node (ref "U2") (pin "5") (pinfunction "2Q3_5") (pintype "output"))
      (node (ref "U3") (pin "31") (pinfunction "A10_31") (pintype "input"))
    )
    (net (code "74") (name "Net-(U2A-2Q4)") (class "Default")
      (node (ref "U2") (pin "6") (pinfunction "2Q4_6") (pintype "output"))
      (node (ref "U3") (pin "32") (pinfunction "A11_32") (pintype "input"))
    )
    (net (code "75") (name "Net-(U2A-2Q5)") (class "Default")
      (node (ref "U2") (pin "8") (pinfunction "2Q5_8") (pintype "output"))
      (node (ref "U3") (pin "33") (pinfunction "A12_33") (pintype "input"))
    )
    (net (code "76") (name "Net-(U2A-2Q6)") (class "Default")
      (node (ref "U2") (pin "9") (pinfunction "2Q6_9") (pintype "output"))
      (node (ref "U3") (pin "34") (pinfunction "A13_34") (pintype "input"))
    )
    (net (code "77") (name "Net-(U2A-2Q7)") (class "Default")
      (node (ref "U2") (pin "11") (pinfunction "2Q7_11") (pintype "output"))
      (node (ref "U3") (pin "35") (pinfunction "A14_35") (pintype "input"))
    )
    (net (code "78") (name "Net-(U3-DQ12)") (class "Default")
      (node (ref "R1") (pin "2") (pinfunction "2_2") (pintype "passive"))
      (node (ref "U3") (pin "43") (pinfunction "DQ12_43") (pintype "bidirectional"))
      (node (ref "U3") (pin "44") (pinfunction "DQ13_44") (pintype "bidirectional"))
      (node (ref "U3") (pin "45") (pinfunction "DQ14_45") (pintype "bidirectional"))
      (node (ref "U3") (pin "46") (pinfunction "DQ15_46") (pintype "bidirectional"))
    )
    (net (code "79") (name "START-MEMORY") (class "Default")
      (node (ref "DL1") (pin "1") (pinfunction "IN_1") (pintype "input"))
      (node (ref "IC1") (pin "6") (pinfunction "1Y_6") (pintype "output"))
    )
    (net (code "80") (name "TIMING-PULSE-3") (class "Default")
      (node (ref "DL2") (pin "1") (pinfunction "IN_1") (pintype "input"))
      (node (ref "IC1") (pin "4") (pinfunction "2Y_4") (pintype "output"))
    )
    (net (code "81") (name "VCC") (class "Default")
      (node (ref "C10") (pin "1") (pinfunction "1_1") (pintype "passive"))
      (node (ref "C11") (pin "1") (pinfunction "1_1") (pintype "passive"))
      (node (ref "C12") (pin "1") (pinfunction "1_1") (pintype "passive"))
      (node (ref "C13") (pin "1") (pinfunction "1_1") (pintype "passive"))
      (node (ref "C14") (pin "1") (pinfunction "1_1") (pintype "passive"))
      (node (ref "C15") (pin "1") (pinfunction "1_1") (pintype "passive"))
      (node (ref "C16") (pin "1") (pinfunction "1_1") (pintype "passive"))
      (node (ref "C21") (pin "1") (pinfunction "1_1") (pintype "passive"))
      (node (ref "C22") (pin "1") (pinfunction "1_1") (pintype "passive"))
      (node (ref "C3") (pin "1") (pinfunction "C1_1") (pintype "passive"))
      (node (ref "C5") (pin "1") (pinfunction "1_1") (pintype "passive"))
      (node (ref "C6") (pin "1") (pinfunction "1_1") (pintype "passive"))
      (node (ref "C7") (pin "1") (pinfunction "1_1") (pintype "passive"))
      (node (ref "C8") (pin "1") (pinfunction "1_1") (pintype "passive"))
      (node (ref "C9") (pin "1") (pinfunction "1_1") (pintype "passive"))
      (node (ref "DL1") (pin "14") (pinfunction "VCC_14") (pintype "power_in"))
      (node (ref "DL2") (pin "14") (pinfunction "VCC_14") (pintype "power_in"))
      (node (ref "IC1") (pin "5") (pinfunction "VCC_5") (pintype "power_in"))
      (node (ref "IC2") (pin "14") (pinfunction "VCC_14") (pintype "power_in"))
      (node (ref "U1") (pin "18") (pinfunction "VCC_18") (pintype "power_in"))
      (node (ref "U1") (pin "31") (pinfunction "VCC_31") (pintype "power_in"))
      (node (ref "U1") (pin "42") (pinfunction "VCC_42") (pintype "power_in"))
      (node (ref "U1") (pin "7") (pinfunction "VCC_7") (pintype "power_in"))
      (node (ref "U2") (pin "18") (pinfunction "VCC_18") (pintype "power_in"))
      (node (ref "U2") (pin "31") (pinfunction "VCC_31") (pintype "power_in"))
      (node (ref "U2") (pin "42") (pinfunction "VCC_42") (pintype "power_in"))
      (node (ref "U2") (pin "7") (pinfunction "VCC_7") (pintype "power_in"))
      (node (ref "U3") (pin "13") (pinfunction "VCC_13") (pintype "power_in"))
      (node (ref "U3") (pin "41") (pinfunction "VCC_41") (pintype "power_in"))
      (node (ref "VR1") (pin "3") (pinfunction "OUT_3") (pintype "power_in"))
    )
    (net (code "82") (name "WRITE-ENABLE") (class "Default")
      (node (ref "DL2") (pin "10") (pinfunction "TAP7_10") (pintype "output"))
      (node (ref "IC2") (pin "5") (pinfunction "3A_5") (pintype "input"))
      (node (ref "U3") (pin "49") (pinfunction "~{OE}_49") (pintype "input"))
    )
    (net (code "83") (name "unconnected-(DL1-NC-Pad2)") (class "Default")
      (node (ref "DL1") (pin "2") (pinfunction "NC_2") (pintype "no_connect"))
    )
    (net (code "84") (name "unconnected-(DL1-TAP1-Pad13)") (class "Default")
      (node (ref "DL1") (pin "13") (pinfunction "TAP1_13") (pintype "output"))
    )
    (net (code "85") (name "unconnected-(DL1-TAP2-Pad3)") (class "Default")
      (node (ref "DL1") (pin "3") (pinfunction "TAP2_3") (pintype "output"))
    )
    (net (code "86") (name "unconnected-(DL1-TAP3-Pad12)") (class "Default")
      (node (ref "DL1") (pin "12") (pinfunction "TAP3_12") (pintype "output"))
    )
    (net (code "87") (name "unconnected-(DL1-TAP5-Pad11)") (class "Default")
      (node (ref "DL1") (pin "11") (pinfunction "TAP5_11") (pintype "output"))
    )
    (net (code "88") (name "unconnected-(DL1-TAP6-Pad5)") (class "Default")
      (node (ref "DL1") (pin "5") (pinfunction "TAP6_5") (pintype "output"))
    )
    (net (code "89") (name "unconnected-(DL1-TAP7-Pad10)") (class "Default")
      (node (ref "DL1") (pin "10") (pinfunction "TAP7_10") (pintype "output"))
    )
    (net (code "90") (name "unconnected-(DL1-TAP8-Pad6)") (class "Default")
      (node (ref "DL1") (pin "6") (pinfunction "TAP8_6") (pintype "output"))
    )
    (net (code "91") (name "unconnected-(DL2-NC-Pad2)") (class "Default")
      (node (ref "DL2") (pin "2") (pinfunction "NC_2") (pintype "no_connect"))
    )
    (net (code "92") (name "unconnected-(DL2-TAP1-Pad13)") (class "Default")
      (node (ref "DL2") (pin "13") (pinfunction "TAP1_13") (pintype "output"))
    )
    (net (code "93") (name "unconnected-(DL2-TAP2-Pad3)") (class "Default")
      (node (ref "DL2") (pin "3") (pinfunction "TAP2_3") (pintype "output"))
    )
    (net (code "94") (name "unconnected-(DL2-TAP3-Pad12)") (class "Default")
      (node (ref "DL2") (pin "12") (pinfunction "TAP3_12") (pintype "output"))
    )
    (net (code "95") (name "unconnected-(DL2-TAP4-Pad4)") (class "Default")
      (node (ref "DL2") (pin "4") (pinfunction "TAP4_4") (pintype "output"))
    )
    (net (code "96") (name "unconnected-(DL2-TAP5-Pad11)") (class "Default")
      (node (ref "DL2") (pin "11") (pinfunction "TAP5_11") (pintype "output"))
    )
    (net (code "97") (name "unconnected-(DL2-TAP8-Pad6)") (class "Default")
      (node (ref "DL2") (pin "6") (pinfunction "TAP8_6") (pintype "output"))
    )
    (net (code "98") (name "unconnected-(DL2-TAP9-Pad9)") (class "Default")
      (node (ref "DL2") (pin "9") (pinfunction "TAP9_9") (pintype "output"))
    )
    (net (code "99") (name "unconnected-(IC2-4Y-Pad8)") (class "Default")
      (node (ref "IC2") (pin "8") (pinfunction "4Y_8") (pintype "output"))
    )
    (net (code "100") (name "unconnected-(IC2-5Y-Pad10)") (class "Default")
      (node (ref "IC2") (pin "10") (pinfunction "5Y_10") (pintype "output"))
    )
    (net (code "101") (name "unconnected-(IC2-6Y-Pad12)") (class "Default")
      (node (ref "IC2") (pin "12") (pinfunction "6Y_12") (pintype "output"))
    )
    (net (code "102") (name "unconnected-(N20-Pad1)") (class "Default")
      (node (ref "N20") (pin "1") (pinfunction "1_1") (pintype "passive"))
    )
    (net (code "103") (name "unconnected-(N20-Pad2)") (class "Default")
      (node (ref "N20") (pin "2") (pinfunction "2_2") (pintype "passive"))
    )
    (net (code "104") (name "unconnected-(N21-Pad1)") (class "Default")
      (node (ref "N21") (pin "1") (pinfunction "1_1") (pintype "passive"))
    )
    (net (code "105") (name "unconnected-(N21-Pad2)") (class "Default")
      (node (ref "N21") (pin "2") (pinfunction "2_2") (pintype "passive"))
    )
    (net (code "106") (name "unconnected-(N22-Pad1)") (class "Default")
      (node (ref "N22") (pin "1") (pinfunction "1_1") (pintype "passive"))
    )
    (net (code "107") (name "unconnected-(N22-Pad2)") (class "Default")
      (node (ref "N22") (pin "2") (pinfunction "2_2") (pintype "passive"))
    )
    (net (code "108") (name "unconnected-(N23-Pad1)") (class "Default")
      (node (ref "N23") (pin "1") (pinfunction "1_1") (pintype "passive"))
    )
    (net (code "109") (name "unconnected-(N23-Pad2)") (class "Default")
      (node (ref "N23") (pin "2") (pinfunction "2_2") (pintype "passive"))
    )
    (net (code "110") (name "unconnected-(N23-Pad4)") (class "Default")
      (node (ref "N23") (pin "4") (pinfunction "4_4") (pintype "passive"))
    )
    (net (code "111") (name "unconnected-(U$1AF-1-PadT2)") (class "Default")
      (node (ref "U$1") (pin "T2") (pinfunction "1_T2") (pintype "bidirectional"))
    )
    (net (code "112") (name "unconnected-(U$1D-1-PadB2)") (class "Default")
      (node (ref "U$1") (pin "B2") (pinfunction "1_B2") (pintype "bidirectional"))
    )
    (net (code "113") (name "unconnected-(U1A-2Q5-Pad8)") (class "Default")
      (node (ref "U1") (pin "8") (pinfunction "2Q5_8") (pintype "output"))
    )
    (net (code "114") (name "unconnected-(U1A-2Q6-Pad9)") (class "Default")
      (node (ref "U1") (pin "9") (pinfunction "2Q6_9") (pintype "output"))
    )
    (net (code "115") (name "unconnected-(U1A-2Q7-Pad11)") (class "Default")
      (node (ref "U1") (pin "11") (pinfunction "2Q7_11") (pintype "output"))
    )
    (net (code "116") (name "unconnected-(U1A-2Q8-Pad12)") (class "Default")
      (node (ref "U1") (pin "12") (pinfunction "2Q8_12") (pintype "output"))
    )
    (net (code "117") (name "unconnected-(U2A-2Q8-Pad12)") (class "Default")
      (node (ref "U2") (pin "12") (pinfunction "2Q8_12") (pintype "output"))
    )
    (net (code "118") (name "unconnected-(U3-INT-Pad1)") (class "Default")
      (node (ref "U3") (pin "1") (pinfunction "INT_1") (pintype "output"))
    )
    (net (code "119") (name "unconnected-(U3-NC-Pad2)") (class "Default")
      (node (ref "U3") (pin "2") (pinfunction "NC_2") (pintype "no_connect"))
    )
    (net (code "120") (name "unconnected-(U3-NC-Pad25)") (class "Default")
      (node (ref "U3") (pin "25") (pinfunction "NC_25") (pintype "no_connect"))
    )
    (net (code "121") (name "unconnected-(U3-NC-Pad30)") (class "Default")
      (node (ref "U3") (pin "30") (pinfunction "NC_30") (pintype "no_connect"))
    )
    (net (code "122") (name "unconnected-(U3-NC-Pad53)") (class "Default")
      (node (ref "U3") (pin "53") (pinfunction "NC_53") (pintype "no_connect"))
    )
    (net (code "123") (name "unconnected-(U3-VRTCBAT-Pad28)") (class "Default")
      (node (ref "U3") (pin "28") (pinfunction "VRTCBAT_28") (pintype "passive"))
    )
    (net (code "124") (name "unconnected-(U3-VRTCCAP-Pad29)") (class "Default")
      (node (ref "U3") (pin "29") (pinfunction "VRTCCAP_29") (pintype "passive"))
    )
    (net (code "125") (name "unconnected-(U3-XIN-Pad27)") (class "Default")
      (node (ref "U3") (pin "27") (pinfunction "XIN_27") (pintype "passive"))
    )
    (net (code "126") (name "unconnected-(U3-XOUT-Pad26)") (class "Default")
      (node (ref "U3") (pin "26") (pinfunction "XOUT_26") (pintype "passive"))
    )
    (net (code "127") (name "unconnected-(U3-~{HSB}-Pad54)") (class "Default")
      (node (ref "U3") (pin "54") (pinfunction "~{HSB}_54") (pintype "bidirectional"))
    )
    (net (code "128") (name "unconnected-(U4A-2Q5-Pad19)") (class "Default")
      (node (ref "U4") (pin "19") (pinfunction "2Q5_19") (pintype "output"))
    )
    (net (code "129") (name "unconnected-(U4A-2Q6-Pad20)") (class "Default")
      (node (ref "U4") (pin "20") (pinfunction "2Q6_20") (pintype "output"))
    )
    (net (code "130") (name "unconnected-(U4A-2Q7-Pad22)") (class "Default")
      (node (ref "U4") (pin "22") (pinfunction "2Q7_22") (pintype "output"))
    )
    (net (code "131") (name "unconnected-(U4A-2Q8-Pad23)") (class "Default")
      (node (ref "U4") (pin "23") (pinfunction "2Q8_23") (pintype "output"))
    )
    (net (code "132") (name "~{MEM-DONE}") (class "Default")
      (node (ref "DL2") (pin "8") (pinfunction "TAP10_8") (pintype "output"))
      (node (ref "IC2") (pin "3") (pinfunction "2A_3") (pintype "input"))
    )
    (net (code "133") (name "~{POWER-OK}") (class "Default")
      (node (ref "U3") (pin "8") (pinfunction "~{CE}_8") (pintype "bidirectional"))
      (node (ref "U5") (pin "2") (pinfunction "~{RESET}_2") (pintype "passive"))
    )
    (net (code "134") (name "~{STROBE}") (class "Default")
      (node (ref "DL1") (pin "8") (pinfunction "TAP10_8") (pintype "output"))
      (node (ref "IC2") (pin "1") (pinfunction "1A_1") (pintype "input"))
    )
    (net (code "135") (name "~{WRITE-ENABLE}") (class "Default")
      (node (ref "IC2") (pin "6") (pinfunction "3Y_6") (pintype "output"))
      (node (ref "U3") (pin "19") (pinfunction "~{WE}_19") (pintype "input"))
    )
  )
)
